# eps_power.net
KiCad netlist of a schematic drawn in Altium Designer
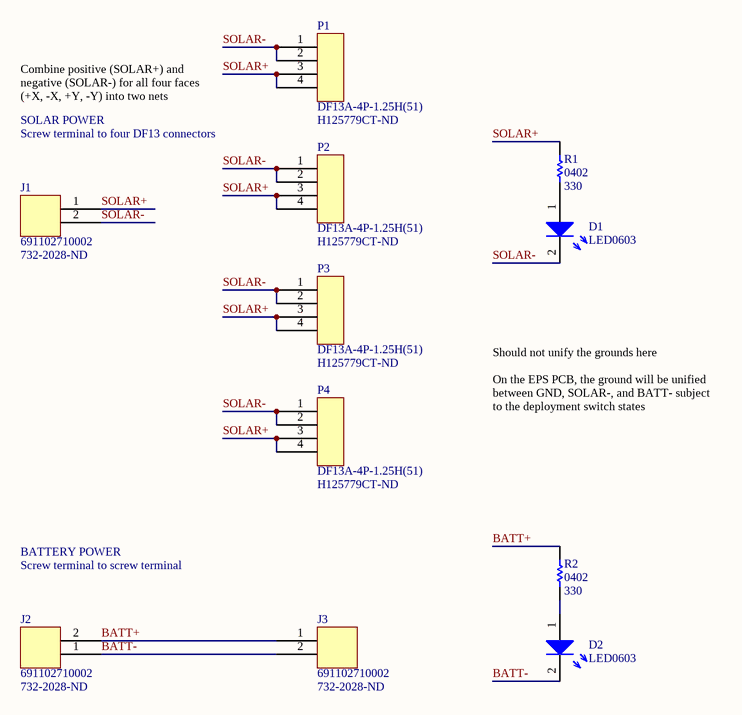
[diagram p0: eps_power.SchDoc]

(export (version "E")
  (design (tool "Eeschema 10.0.6"))
  (components
    (comp (ref "D1")
      (value "LED0603")
      (footprint "LED0603")
      (description "Generic 0603 LED. Use ChipLED from Osram for generic ones.")
      (libsource (lib "heron-general") (part "LED0603"))
    )
    (comp (ref "D2")
      (value "LED0603")
      (footprint "LED0603")
      (description "Generic 0603 LED. Use ChipLED from Osram for generic ones.")
      (libsource (lib "heron-general") (part "LED0603"))
    )
    (comp (ref "J1")
      (value "691102710002")
      (footprint "CON2_SCREW_5.00MM_691102710002")
      (description "2-POS screw terminal, 5mm pitch")
      (fields (field (name "SUPPLIER PART NUMBER 1") "732-2028-ND"))
      (libsource (lib "") (part "691102710002_2"))
    )
    (comp (ref "J2")
      (value "691102710002")
      (footprint "CON2_SCREW_5.00MM_691102710002")
      (description "2-POS screw terminal, 5mm pitch")
      (fields (field (name "SUPPLIER PART NUMBER 1") "732-2028-ND"))
      (libsource (lib "") (part "691102710002_1"))
    )
    (comp (ref "J3")
      (value "691102710002")
      (footprint "CON2_SCREW_5.00MM_691102710002")
      (description "2-POS screw terminal, 5mm pitch")
      (fields (field (name "SUPPLIER PART NUMBER 1") "732-2028-ND"))
      (libsource (lib "heron-general") (part "691102710002"))
    )
    (comp (ref "P1")
      (value "DF13A-4P-1.25H(51)")
      (footprint "DF13A-4P-1.25H(51)")
      (description "4 pos DF13 right angle surface mount connector")
      (fields (field (name "SUPPLIER PART NUMBER 1") "H125779CT-ND"))
      (libsource (lib "heron-general") (part "DF13A-4P-1.25H(51)"))
    )
    (comp (ref "P2")
      (value "DF13A-4P-1.25H(51)")
      (footprint "DF13A-4P-1.25H(51)")
      (description "4 pos DF13 right angle surface mount connector")
      (fields (field (name "SUPPLIER PART NUMBER 1") "H125779CT-ND"))
      (libsource (lib "heron-general") (part "DF13A-4P-1.25H(51)"))
    )
    (comp (ref "P3")
      (value "DF13A-4P-1.25H(51)")
      (footprint "DF13A-4P-1.25H(51)")
      (description "4 pos DF13 right angle surface mount connector")
      (fields (field (name "SUPPLIER PART NUMBER 1") "H125779CT-ND"))
      (libsource (lib "heron-general") (part "DF13A-4P-1.25H(51)"))
    )
    (comp (ref "P4")
      (value "DF13A-4P-1.25H(51)")
      (footprint "DF13A-4P-1.25H(51)")
      (description "4 pos DF13 right angle surface mount connector")
      (fields (field (name "SUPPLIER PART NUMBER 1") "H125779CT-ND"))
      (libsource (lib "heron-general") (part "DF13A-4P-1.25H(51)"))
    )
    (comp (ref "R1")
      (value "0402")
      (footprint "RES0402R")
      (description "0402 resistor")
      (fields (field (name "ALTIUM_VALUE") "330"))
      (libsource (lib "heron-general") (part "RES0402"))
    )
    (comp (ref "R2")
      (value "0402")
      (footprint "RES0402R")
      (description "0402 resistor")
      (fields (field (name "ALTIUM_VALUE") "330"))
      (libsource (lib "heron-general") (part "RES0402"))
    )
  )
  (nets
    (net (code "1") (name "/BATT+") (class "Default")
      (node (ref "J2") (pin "2") (pinfunction "2_2") (pintype "passive"))
      (node (ref "J3") (pin "1") (pinfunction "1_1") (pintype "passive"))
      (node (ref "R2") (pin "2") (pinfunction "2_2") (pintype "passive"))
    )
    (net (code "2") (name "/BATT-") (class "Default")
      (node (ref "D2") (pin "2") (pinfunction "2_2") (pintype "passive"))
      (node (ref "J2") (pin "1") (pinfunction "1_1") (pintype "passive"))
      (node (ref "J3") (pin "2") (pinfunction "2_2") (pintype "passive"))
    )
    (net (code "3") (name "/SOLAR+") (class "Default")
      (node (ref "J1") (pin "1") (pinfunction "1_1") (pintype "passive"))
      (node (ref "P1") (pin "3") (pintype "passive"))
      (node (ref "P1") (pin "4") (pintype "passive"))
      (node (ref "P2") (pin "3") (pintype "passive"))
      (node (ref "P2") (pin "4") (pintype "passive"))
      (node (ref "P3") (pin "3") (pintype "passive"))
      (node (ref "P3") (pin "4") (pintype "passive"))
      (node (ref "P4") (pin "3") (pintype "passive"))
      (node (ref "P4") (pin "4") (pintype "passive"))
      (node (ref "R1") (pin "1") (pinfunction "1_1") (pintype "passive"))
    )
    (net (code "4") (name "/SOLAR-") (class "Default")
      (node (ref "D1") (pin "2") (pinfunction "2_2") (pintype "passive"))
      (node (ref "J1") (pin "2") (pinfunction "2_2") (pintype "passive"))
      (node (ref "P1") (pin "1") (pintype "passive"))
      (node (ref "P1") (pin "2") (pintype "passive"))
      (node (ref "P2") (pin "1") (pintype "passive"))
      (node (ref "P2") (pin "2") (pintype "passive"))
      (node (ref "P3") (pin "1") (pintype "passive"))
      (node (ref "P3") (pin "2") (pintype "passive"))
      (node (ref "P4") (pin "1") (pintype "passive"))
      (node (ref "P4") (pin "2") (pintype "passive"))
    )
    (net (code "5") (name "Net-(D1-Pad1)") (class "Default")
      (node (ref "D1") (pin "1") (pinfunction "1_1") (pintype "passive"))
      (node (ref "R1") (pin "2") (pinfunction "2_2") (pintype "passive"))
    )
    (net (code "6") (name "Net-(D2-Pad1)") (class "Default")
      (node (ref "D2") (pin "1") (pinfunction "1_1") (pintype "passive"))
      (node (ref "R2") (pin "1") (pinfunction "1_1") (pintype "passive"))
    )
  )
)
